# FLUIDIC_CTRL.net
KiCad netlist of a schematic drawn in Altium Designer
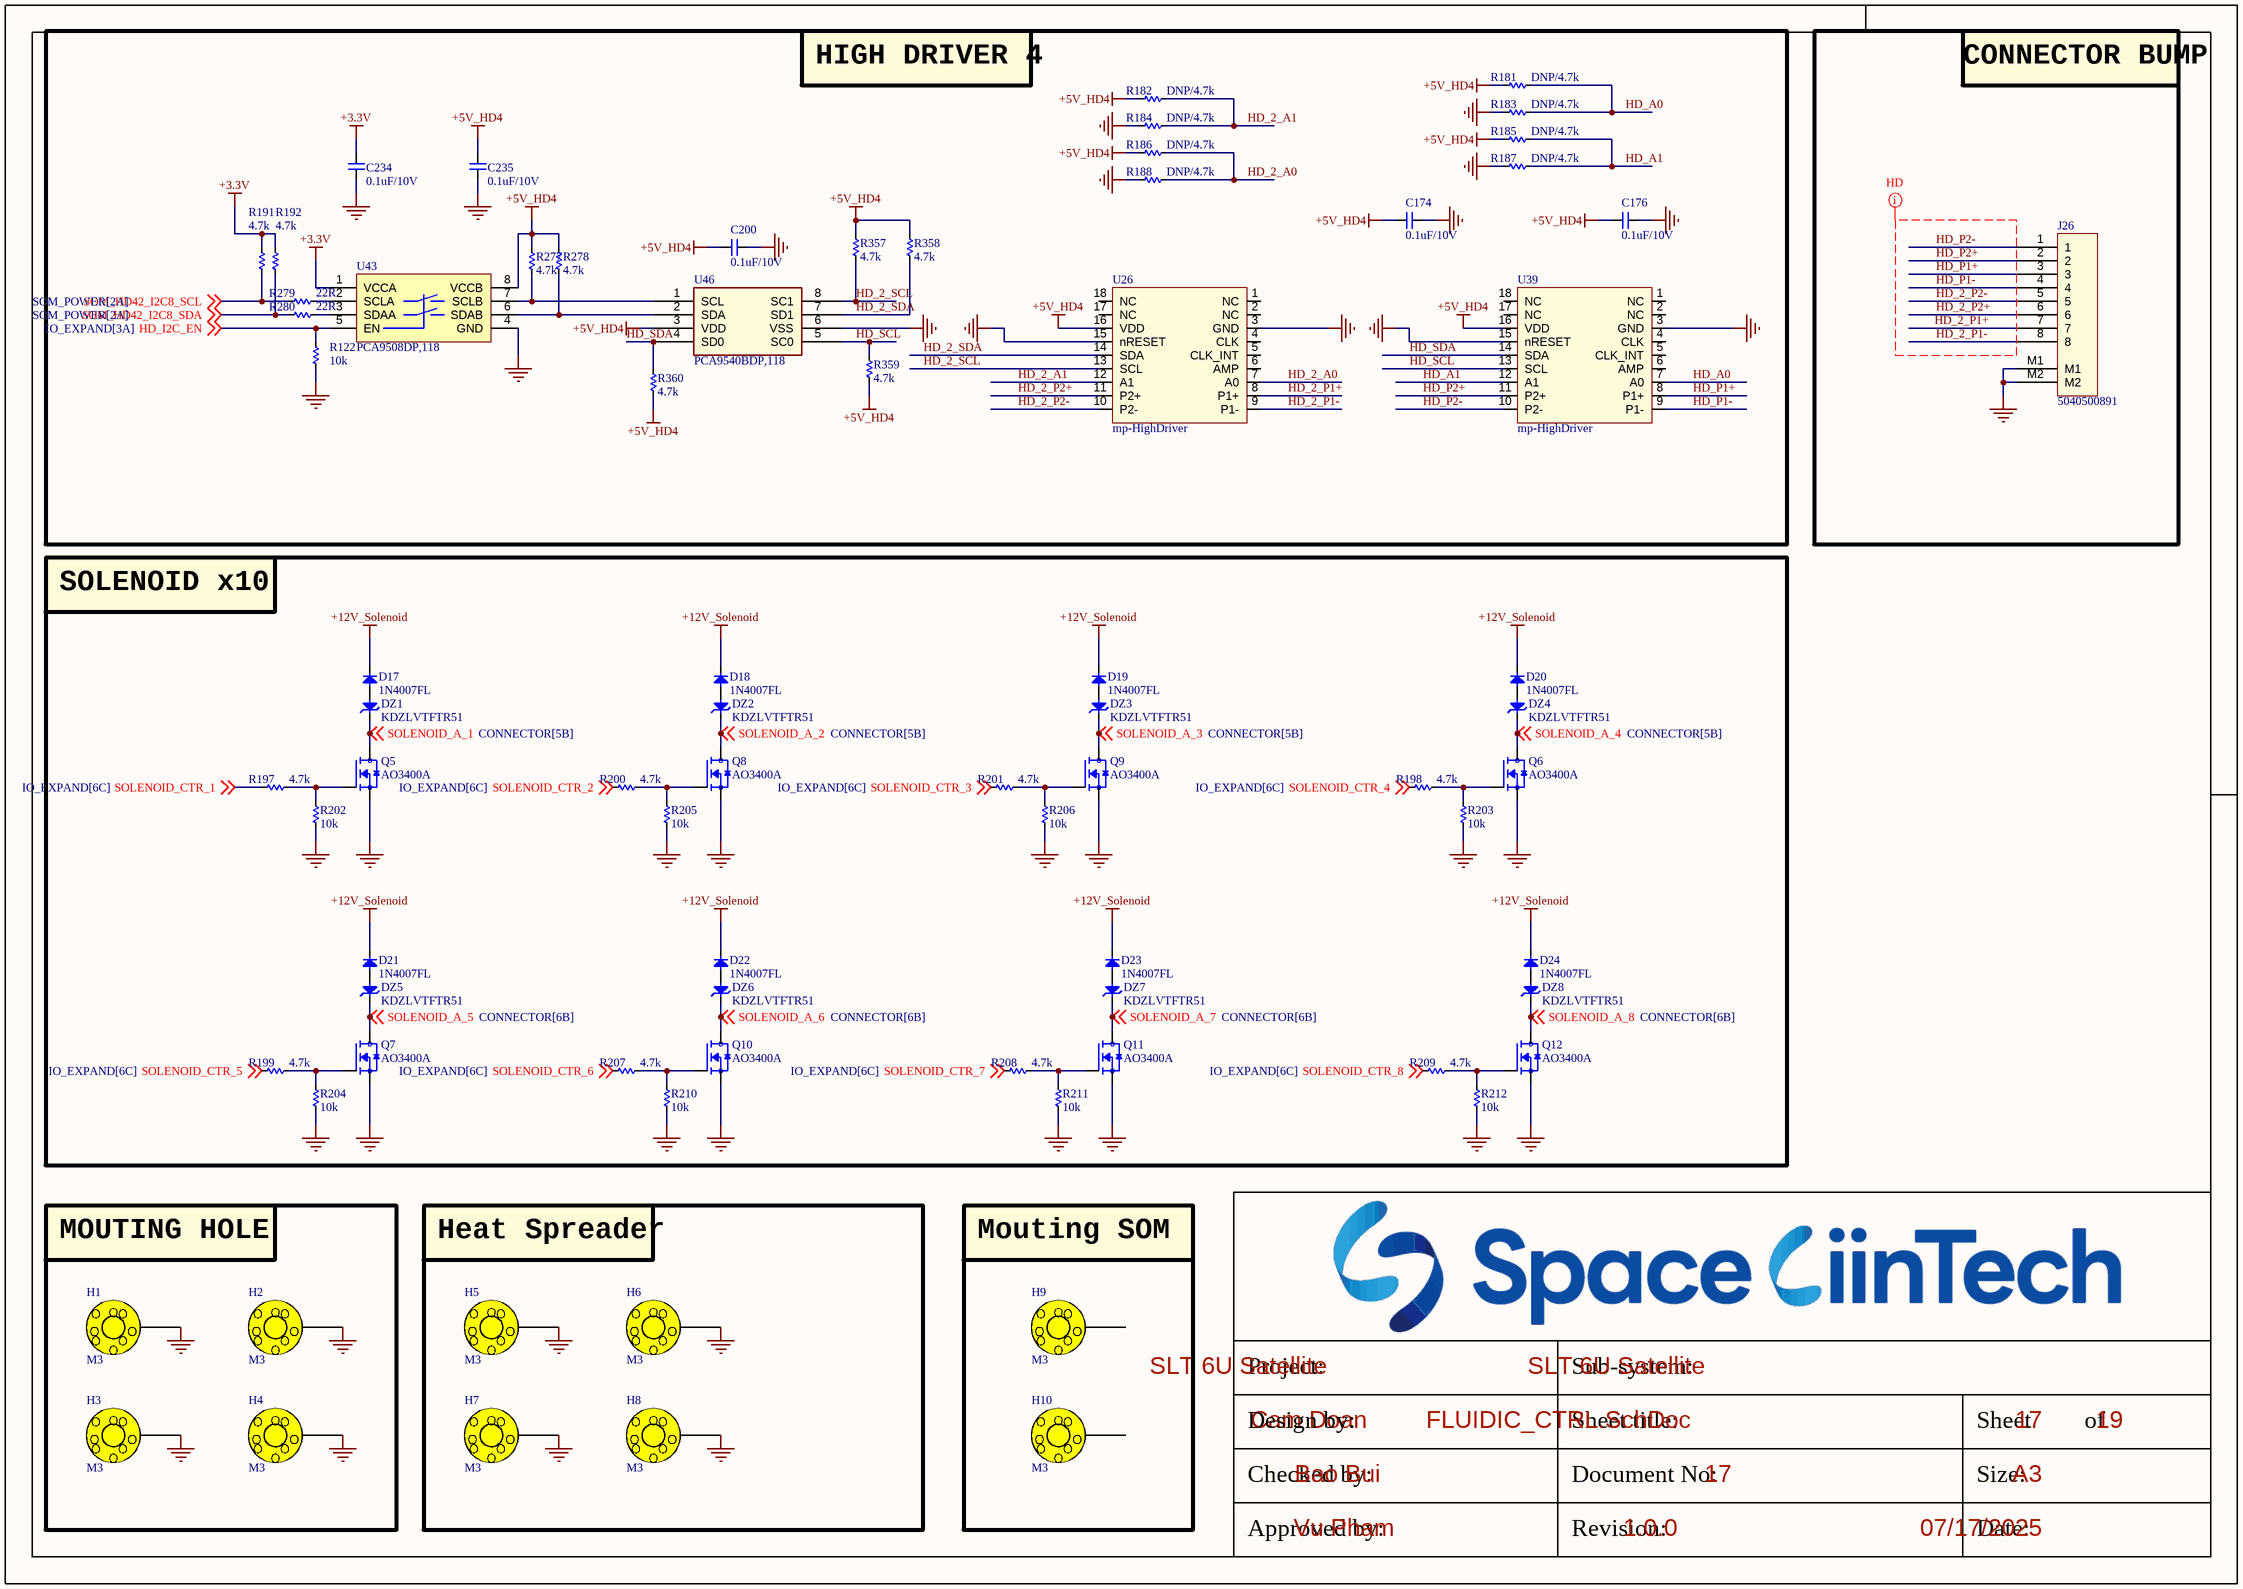
[diagram p0: FLUIDIC_CTRL.SchDoc]

(export (version "E")
  (design (tool "Eeschema 10.0.6"))
  (components
    (comp (ref "C174")
      (value "0.1uF/10V")
      (footprint "CAP_C_1005X60")
      (description "CAP CHIP")
      (libsource (lib "LABLIB") (part "_CAP_C_2"))
    )
    (comp (ref "C176")
      (value "0.1uF/10V")
      (footprint "CAP_C_1005X60")
      (description "CAP CHIP")
      (libsource (lib "LABLIB") (part "_CAP_C_2"))
    )
    (comp (ref "C200")
      (value "0.1uF/10V")
      (footprint "CAP_C_1005X60")
      (description "CAP CHIP")
      (libsource (lib "LABLIB") (part "_CAP_C_2"))
    )
    (comp (ref "C234")
      (value "0.1uF/10V")
      (footprint "CAP_C_1005X60")
      (description "CAP CHIP")
      (libsource (lib "LABLIB") (part "_CAP_C_2"))
    )
    (comp (ref "C235")
      (value "0.1uF/10V")
      (footprint "CAP_C_1005X60")
      (description "CAP CHIP")
      (libsource (lib "LABLIB") (part "_CAP_C_2"))
    )
    (comp (ref "D17")
      (value "1N4007FL")
      (footprint "DIO-SMD-106")
      (description "Default Diode")
      (fields (field (name "PUBLISHER") "Altium Limited"))
      (libsource (lib "LABLIB") (part "Diode SMD"))
    )
    (comp (ref "D18")
      (value "1N4007FL")
      (footprint "DIO-SMD-106")
      (description "Default Diode")
      (fields (field (name "PUBLISHER") "Altium Limited"))
      (libsource (lib "LABLIB") (part "Diode SMD"))
    )
    (comp (ref "D19")
      (value "1N4007FL")
      (footprint "DIO-SMD-106")
      (description "Default Diode")
      (fields (field (name "PUBLISHER") "Altium Limited"))
      (libsource (lib "LABLIB") (part "Diode SMD"))
    )
    (comp (ref "D20")
      (value "1N4007FL")
      (footprint "DIO-SMD-106")
      (description "Default Diode")
      (fields (field (name "PUBLISHER") "Altium Limited"))
      (libsource (lib "LABLIB") (part "Diode SMD"))
    )
    (comp (ref "D21")
      (value "1N4007FL")
      (footprint "DIO-SMD-106")
      (description "Default Diode")
      (fields (field (name "PUBLISHER") "Altium Limited"))
      (libsource (lib "LABLIB") (part "Diode SMD"))
    )
    (comp (ref "D22")
      (value "1N4007FL")
      (footprint "DIO-SMD-106")
      (description "Default Diode")
      (fields (field (name "PUBLISHER") "Altium Limited"))
      (libsource (lib "LABLIB") (part "Diode SMD"))
    )
    (comp (ref "D23")
      (value "1N4007FL")
      (footprint "DIO-SMD-106")
      (description "Default Diode")
      (fields (field (name "PUBLISHER") "Altium Limited"))
      (libsource (lib "LABLIB") (part "Diode SMD"))
    )
    (comp (ref "D24")
      (value "1N4007FL")
      (footprint "DIO-SMD-106")
      (description "Default Diode")
      (fields (field (name "PUBLISHER") "Altium Limited"))
      (libsource (lib "LABLIB") (part "Diode SMD"))
    )
    (comp (ref "DZ1")
      (value "KDZLVTFTR51")
      (footprint "DIO-0.5A-SMALL")
      (description "Zenner")
      (libsource (lib "LABLIB") (part "DIODE Zener"))
    )
    (comp (ref "DZ2")
      (value "KDZLVTFTR51")
      (footprint "DIO-0.5A-SMALL")
      (description "Zenner")
      (libsource (lib "LABLIB") (part "DIODE Zener"))
    )
    (comp (ref "DZ3")
      (value "KDZLVTFTR51")
      (footprint "DIO-0.5A-SMALL")
      (description "Zenner")
      (libsource (lib "LABLIB") (part "DIODE Zener"))
    )
    (comp (ref "DZ4")
      (value "KDZLVTFTR51")
      (footprint "DIO-0.5A-SMALL")
      (description "Zenner")
      (libsource (lib "LABLIB") (part "DIODE Zener"))
    )
    (comp (ref "DZ5")
      (value "KDZLVTFTR51")
      (footprint "DIO-0.5A-SMALL")
      (description "Zenner")
      (libsource (lib "LABLIB") (part "DIODE Zener"))
    )
    (comp (ref "DZ6")
      (value "KDZLVTFTR51")
      (footprint "DIO-0.5A-SMALL")
      (description "Zenner")
      (libsource (lib "LABLIB") (part "DIODE Zener"))
    )
    (comp (ref "DZ7")
      (value "KDZLVTFTR51")
      (footprint "DIO-0.5A-SMALL")
      (description "Zenner")
      (libsource (lib "LABLIB") (part "DIODE Zener"))
    )
    (comp (ref "DZ8")
      (value "KDZLVTFTR51")
      (footprint "DIO-0.5A-SMALL")
      (description "Zenner")
      (libsource (lib "LABLIB") (part "DIODE Zener"))
    )
    (comp (ref "H1") (value "M3") (footprint "HEX-M3") (libsource (lib "hex_M3") (part "HEX-M3")))
    (comp (ref "H2") (value "M3") (footprint "HEX-M3") (libsource (lib "hex_M3") (part "HEX-M3")))
    (comp (ref "H3") (value "M3") (footprint "HEX-M3") (libsource (lib "hex_M3") (part "HEX-M3")))
    (comp (ref "H4") (value "M3") (footprint "HEX-M3") (libsource (lib "hex_M3") (part "HEX-M3")))
    (comp (ref "H5") (value "M3") (footprint "HEX-M3") (libsource (lib "hex_M3") (part "HEX-M3")))
    (comp (ref "H6") (value "M3") (footprint "HEX-M3") (libsource (lib "hex_M3") (part "HEX-M3")))
    (comp (ref "H7") (value "M3") (footprint "HEX-M3") (libsource (lib "hex_M3") (part "HEX-M3")))
    (comp (ref "H8") (value "M3") (footprint "HEX-M3") (libsource (lib "hex_M3") (part "HEX-M3")))
    (comp (ref "H9")
      (value "M3")
      (footprint "Testpoint_TH_D400H200")
      (libsource (lib "hex_M3") (part "HEX-M3"))
    )
    (comp (ref "H10")
      (value "M3")
      (footprint "Testpoint_TH_D400H200")
      (libsource (lib "hex_M3") (part "HEX-M3"))
    )
    (comp (ref "J26")
      (value "5040500891")
      (footprint "MOLEX_5040500891")
      (libsource (lib "LABLIB") (part "Header 8x1_2M"))
    )
    (comp (ref "Q5")
      (value "AO3400A")
      (footprint "SOT95P240X120-3N")
      (description "N-Channel 30 V 5.7A (Ta) 1.4W (Ta) Surface Mount SOT-23-3")
      (fields (field (name "MF") "Alpha & Omega Semiconductor"))
      (libsource (lib "new_component") (part "MOSFET_N"))
    )
    (comp (ref "Q6")
      (value "AO3400A")
      (footprint "SOT95P240X120-3N")
      (description "N-Channel 30 V 5.7A (Ta) 1.4W (Ta) Surface Mount SOT-23-3")
      (fields (field (name "MF") "Alpha & Omega Semiconductor"))
      (libsource (lib "new_component") (part "MOSFET_N"))
    )
    (comp (ref "Q7")
      (value "AO3400A")
      (footprint "SOT95P240X120-3N")
      (description "N-Channel 30 V 5.7A (Ta) 1.4W (Ta) Surface Mount SOT-23-3")
      (fields (field (name "MF") "Alpha & Omega Semiconductor"))
      (libsource (lib "new_component") (part "MOSFET_N"))
    )
    (comp (ref "Q8")
      (value "AO3400A")
      (footprint "SOT95P240X120-3N")
      (description "N-Channel 30 V 5.7A (Ta) 1.4W (Ta) Surface Mount SOT-23-3")
      (fields (field (name "MF") "Alpha & Omega Semiconductor"))
      (libsource (lib "new_component") (part "MOSFET_N"))
    )
    (comp (ref "Q9")
      (value "AO3400A")
      (footprint "SOT95P240X120-3N")
      (description "N-Channel 30 V 5.7A (Ta) 1.4W (Ta) Surface Mount SOT-23-3")
      (fields (field (name "MF") "Alpha & Omega Semiconductor"))
      (libsource (lib "new_component") (part "MOSFET_N"))
    )
    (comp (ref "Q10")
      (value "AO3400A")
      (footprint "SOT95P240X120-3N")
      (description "N-Channel 30 V 5.7A (Ta) 1.4W (Ta) Surface Mount SOT-23-3")
      (fields (field (name "MF") "Alpha & Omega Semiconductor"))
      (libsource (lib "new_component") (part "MOSFET_N"))
    )
    (comp (ref "Q11")
      (value "AO3400A")
      (footprint "SOT95P240X120-3N")
      (description "N-Channel 30 V 5.7A (Ta) 1.4W (Ta) Surface Mount SOT-23-3")
      (fields (field (name "MF") "Alpha & Omega Semiconductor"))
      (libsource (lib "new_component") (part "MOSFET_N"))
    )
    (comp (ref "Q12")
      (value "AO3400A")
      (footprint "SOT95P240X120-3N")
      (description "N-Channel 30 V 5.7A (Ta) 1.4W (Ta) Surface Mount SOT-23-3")
      (fields (field (name "MF") "Alpha & Omega Semiconductor"))
      (libsource (lib "new_component") (part "MOSFET_N"))
    )
    (comp (ref "R122")
      (value "10k")
      (footprint "RES_C_1005X40")
      (description "RES")
      (libsource (lib "LABLIB") (part "_RES_B_2"))
    )
    (comp (ref "R181")
      (value "DNP/4.7k")
      (footprint "RES_C_1005X40")
      (description "RES")
      (libsource (lib "LABLIB") (part "_RES_B_2"))
    )
    (comp (ref "R182")
      (value "DNP/4.7k")
      (footprint "RES_C_1005X40")
      (description "RES")
      (libsource (lib "LABLIB") (part "_RES_B_2"))
    )
    (comp (ref "R183")
      (value "DNP/4.7k")
      (footprint "RES_C_1005X40")
      (description "RES")
      (libsource (lib "LABLIB") (part "_RES_B_2"))
    )
    (comp (ref "R184")
      (value "DNP/4.7k")
      (footprint "RES_C_1005X40")
      (description "RES")
      (libsource (lib "LABLIB") (part "_RES_B_2"))
    )
    (comp (ref "R185")
      (value "DNP/4.7k")
      (footprint "RES_C_1005X40")
      (description "RES")
      (libsource (lib "LABLIB") (part "_RES_B_2"))
    )
    (comp (ref "R186")
      (value "DNP/4.7k")
      (footprint "RES_C_1005X40")
      (description "RES")
      (libsource (lib "LABLIB") (part "_RES_B_2"))
    )
    (comp (ref "R187")
      (value "DNP/4.7k")
      (footprint "RES_C_1005X40")
      (description "RES")
      (libsource (lib "LABLIB") (part "_RES_B_2"))
    )
    (comp (ref "R188")
      (value "DNP/4.7k")
      (footprint "RES_C_1005X40")
      (description "RES")
      (libsource (lib "LABLIB") (part "_RES_B_2"))
    )
    (comp (ref "R191")
      (value "4.7k")
      (footprint "RES_C_1005X40")
      (description "RES")
      (libsource (lib "LABLIB") (part "_RES_B_2"))
    )
    (comp (ref "R192")
      (value "4.7k")
      (footprint "RES_C_1005X40")
      (description "RES")
      (libsource (lib "LABLIB") (part "_RES_B_2"))
    )
    (comp (ref "R197")
      (value "4.7k")
      (footprint "RES_C_1005X40")
      (description "RES")
      (libsource (lib "LABLIB") (part "_RES_B_2"))
    )
    (comp (ref "R198")
      (value "4.7k")
      (footprint "RES_C_1005X40")
      (description "RES")
      (libsource (lib "LABLIB") (part "_RES_B_2"))
    )
    (comp (ref "R199")
      (value "4.7k")
      (footprint "RES_C_1005X40")
      (description "RES")
      (libsource (lib "LABLIB") (part "_RES_B_2"))
    )
    (comp (ref "R200")
      (value "4.7k")
      (footprint "RES_C_1005X40")
      (description "RES")
      (libsource (lib "LABLIB") (part "_RES_B_2"))
    )
    (comp (ref "R201")
      (value "4.7k")
      (footprint "RES_C_1005X40")
      (description "RES")
      (libsource (lib "LABLIB") (part "_RES_B_2"))
    )
    (comp (ref "R202")
      (value "10k")
      (footprint "RES_C_1005X40")
      (description "RES")
      (libsource (lib "LABLIB") (part "_RES_B_2"))
    )
    (comp (ref "R203")
      (value "10k")
      (footprint "RES_C_1005X40")
      (description "RES")
      (libsource (lib "LABLIB") (part "_RES_B_2"))
    )
    (comp (ref "R204")
      (value "10k")
      (footprint "RES_C_1005X40")
      (description "RES")
      (libsource (lib "LABLIB") (part "_RES_B_2"))
    )
    (comp (ref "R205")
      (value "10k")
      (footprint "RES_C_1005X40")
      (description "RES")
      (libsource (lib "LABLIB") (part "_RES_B_2"))
    )
    (comp (ref "R206")
      (value "10k")
      (footprint "RES_C_1005X40")
      (description "RES")
      (libsource (lib "LABLIB") (part "_RES_B_2"))
    )
    (comp (ref "R207")
      (value "4.7k")
      (footprint "RES_C_1005X40")
      (description "RES")
      (libsource (lib "LABLIB") (part "_RES_B_2"))
    )
    (comp (ref "R208")
      (value "4.7k")
      (footprint "RES_C_1005X40")
      (description "RES")
      (libsource (lib "LABLIB") (part "_RES_B_2"))
    )
    (comp (ref "R209")
      (value "4.7k")
      (footprint "RES_C_1005X40")
      (description "RES")
      (libsource (lib "LABLIB") (part "_RES_B_2"))
    )
    (comp (ref "R210")
      (value "10k")
      (footprint "RES_C_1005X40")
      (description "RES")
      (libsource (lib "LABLIB") (part "_RES_B_2"))
    )
    (comp (ref "R211")
      (value "10k")
      (footprint "RES_C_1005X40")
      (description "RES")
      (libsource (lib "LABLIB") (part "_RES_B_2"))
    )
    (comp (ref "R212")
      (value "10k")
      (footprint "RES_C_1005X40")
      (description "RES")
      (libsource (lib "LABLIB") (part "_RES_B_2"))
    )
    (comp (ref "R277")
      (value "4.7k")
      (footprint "RES_C_1005X40")
      (description "RES")
      (libsource (lib "LABLIB") (part "_RES_B_2"))
    )
    (comp (ref "R278")
      (value "4.7k")
      (footprint "RES_C_1005X40")
      (description "RES")
      (libsource (lib "LABLIB") (part "_RES_B_2"))
    )
    (comp (ref "R279")
      (value "22R")
      (footprint "RES_C_1005X40")
      (description "RES")
      (libsource (lib "LABLIB") (part "_RES_B_2"))
    )
    (comp (ref "R280")
      (value "22R")
      (footprint "RES_C_1005X40")
      (description "RES")
      (libsource (lib "LABLIB") (part "_RES_B_2"))
    )
    (comp (ref "R357")
      (value "4.7k")
      (footprint "RES_C_1005X40")
      (description "RES")
      (libsource (lib "LABLIB") (part "_RES_B_2"))
    )
    (comp (ref "R358")
      (value "4.7k")
      (footprint "RES_C_1005X40")
      (description "RES")
      (libsource (lib "LABLIB") (part "_RES_B_2"))
    )
    (comp (ref "R359")
      (value "4.7k")
      (footprint "RES_C_1005X40")
      (description "RES")
      (libsource (lib "LABLIB") (part "_RES_B_2"))
    )
    (comp (ref "R360")
      (value "4.7k")
      (footprint "RES_C_1005X40")
      (description "RES")
      (libsource (lib "LABLIB") (part "_RES_B_2"))
    )
    (comp (ref "U26")
      (value "mp-HighDriver")
      (footprint "MP_HIGHDRIVER")
      (libsource (lib "new_component") (part "mp-HighDriver"))
    )
    (comp (ref "U39")
      (value "mp-HighDriver")
      (footprint "MP_HIGHDRIVER")
      (libsource (lib "new_component") (part "mp-HighDriver"))
    )
    (comp (ref "U43")
      (value "PCA9508DP,118")
      (footprint "TSOP8")
      (libsource (lib "EXP_HW_V3") (part "PCA9508DP,118"))
    )
    (comp (ref "U46")
      (value "PCA9540BDP,118")
      (footprint "SOP65P510X110X300W-8")
      (description "IC INTERFACE SPECIALIZED")
      (libsource (lib "LABLIB") (part "IC_I2C_Mux_PCA9540BDP,118"))
    )
  )
  (nets
    (net (code "1") (name "+3.3V") (class "Default")
      (node (ref "C234") (pin "2") (pinfunction "2_2") (pintype "passive"))
      (node (ref "R191") (pin "1") (pinfunction "1_1") (pintype "passive"))
      (node (ref "R192") (pin "1") (pinfunction "1_1") (pintype "passive"))
      (node (ref "U43") (pin "1") (pinfunction "VCCA_1") (pintype "passive"))
    )
    (net (code "2") (name "+5V_HD4") (class "Default")
      (node (ref "C174") (pin "2") (pinfunction "2_2") (pintype "passive"))
      (node (ref "C176") (pin "2") (pinfunction "2_2") (pintype "passive"))
      (node (ref "C200") (pin "2") (pinfunction "2_2") (pintype "passive"))
      (node (ref "C235") (pin "2") (pinfunction "2_2") (pintype "passive"))
      (node (ref "R181") (pin "1") (pinfunction "1_1") (pintype "passive"))
      (node (ref "R182") (pin "1") (pinfunction "1_1") (pintype "passive"))
      (node (ref "R185") (pin "1") (pinfunction "1_1") (pintype "passive"))
      (node (ref "R186") (pin "1") (pinfunction "1_1") (pintype "passive"))
      (node (ref "R277") (pin "1") (pinfunction "1_1") (pintype "passive"))
      (node (ref "R278") (pin "1") (pinfunction "1_1") (pintype "passive"))
      (node (ref "R357") (pin "1") (pinfunction "1_1") (pintype "passive"))
      (node (ref "R358") (pin "1") (pinfunction "1_1") (pintype "passive"))
      (node (ref "R359") (pin "1") (pinfunction "1_1") (pintype "passive"))
      (node (ref "R360") (pin "1") (pinfunction "1_1") (pintype "passive"))
      (node (ref "U26") (pin "16") (pinfunction "VDD_16") (pintype "power_in"))
      (node (ref "U39") (pin "16") (pinfunction "VDD_16") (pintype "power_in"))
      (node (ref "U43") (pin "8") (pinfunction "VCCB_8") (pintype "passive"))
      (node (ref "U46") (pin "3") (pinfunction "VDD_3") (pintype "passive"))
    )
    (net (code "3") (name "+12V_Solenoid") (class "Default")
      (node (ref "D17") (pin "1") (pinfunction "K_1") (pintype "passive"))
      (node (ref "D18") (pin "1") (pinfunction "K_1") (pintype "passive"))
      (node (ref "D19") (pin "1") (pinfunction "K_1") (pintype "passive"))
      (node (ref "D20") (pin "1") (pinfunction "K_1") (pintype "passive"))
      (node (ref "D21") (pin "1") (pinfunction "K_1") (pintype "passive"))
      (node (ref "D22") (pin "1") (pinfunction "K_1") (pintype "passive"))
      (node (ref "D23") (pin "1") (pinfunction "K_1") (pintype "passive"))
      (node (ref "D24") (pin "1") (pinfunction "K_1") (pintype "passive"))
    )
    (net (code "4") (name "/HD_2_A0") (class "Default")
      (node (ref "R186") (pin "2") (pinfunction "2_2") (pintype "passive"))
      (node (ref "R188") (pin "2") (pinfunction "2_2") (pintype "passive"))
      (node (ref "U26") (pin "7") (pinfunction "A0_7") (pintype "passive"))
    )
    (net (code "5") (name "/HD_2_A1") (class "Default")
      (node (ref "R182") (pin "2") (pinfunction "2_2") (pintype "passive"))
      (node (ref "R184") (pin "2") (pinfunction "2_2") (pintype "passive"))
      (node (ref "U26") (pin "12") (pinfunction "A1_12") (pintype "passive"))
    )
    (net (code "6") (name "/HD_2_P1+") (class "Default")
      (node (ref "J26") (pin "7") (pinfunction "7_7") (pintype "passive"))
      (node (ref "U26") (pin "8") (pinfunction "P1+_8") (pintype "passive"))
    )
    (net (code "7") (name "/HD_2_P1-") (class "Default")
      (node (ref "J26") (pin "8") (pinfunction "8_8") (pintype "passive"))
      (node (ref "U26") (pin "9") (pinfunction "P1-_9") (pintype "passive"))
    )
    (net (code "8") (name "/HD_2_P2+") (class "Default")
      (node (ref "J26") (pin "6") (pinfunction "6_6") (pintype "passive"))
      (node (ref "U26") (pin "11") (pinfunction "P2+_11") (pintype "passive"))
    )
    (net (code "9") (name "/HD_2_P2-") (class "Default")
      (node (ref "J26") (pin "5") (pinfunction "5_5") (pintype "passive"))
      (node (ref "U26") (pin "10") (pinfunction "P2-_10") (pintype "passive"))
    )
    (net (code "10") (name "/HD_2_SCL") (class "Default")
      (node (ref "R357") (pin "2") (pinfunction "2_2") (pintype "passive"))
      (node (ref "U26") (pin "13") (pinfunction "SCL_13") (pintype "passive"))
      (node (ref "U46") (pin "8") (pinfunction "SC1_8") (pintype "passive"))
    )
    (net (code "11") (name "/HD_2_SDA") (class "Default")
      (node (ref "R358") (pin "2") (pinfunction "2_2") (pintype "passive"))
      (node (ref "U26") (pin "14") (pinfunction "SDA_14") (pintype "passive"))
      (node (ref "U46") (pin "7") (pinfunction "SD1_7") (pintype "passive"))
    )
    (net (code "12") (name "/HD_A0") (class "Default")
      (node (ref "R181") (pin "2") (pinfunction "2_2") (pintype "passive"))
      (node (ref "R183") (pin "2") (pinfunction "2_2") (pintype "passive"))
      (node (ref "U39") (pin "7") (pinfunction "A0_7") (pintype "passive"))
    )
    (net (code "13") (name "/HD_A1") (class "Default")
      (node (ref "R185") (pin "2") (pinfunction "2_2") (pintype "passive"))
      (node (ref "R187") (pin "2") (pinfunction "2_2") (pintype "passive"))
      (node (ref "U39") (pin "12") (pinfunction "A1_12") (pintype "passive"))
    )
    (net (code "14") (name "/HD_P1+") (class "Default")
      (node (ref "J26") (pin "3") (pinfunction "3_3") (pintype "passive"))
      (node (ref "U39") (pin "8") (pinfunction "P1+_8") (pintype "passive"))
    )
    (net (code "15") (name "/HD_P1-") (class "Default")
      (node (ref "J26") (pin "4") (pinfunction "4_4") (pintype "passive"))
      (node (ref "U39") (pin "9") (pinfunction "P1-_9") (pintype "passive"))
    )
    (net (code "16") (name "/HD_P2+") (class "Default")
      (node (ref "J26") (pin "2") (pinfunction "2_2") (pintype "passive"))
      (node (ref "U39") (pin "11") (pinfunction "P2+_11") (pintype "passive"))
    )
    (net (code "17") (name "/HD_P2-") (class "Default")
      (node (ref "J26") (pin "1") (pinfunction "1_1") (pintype "passive"))
      (node (ref "U39") (pin "10") (pinfunction "P2-_10") (pintype "passive"))
    )
    (net (code "18") (name "/HD_SCL") (class "Default")
      (node (ref "R359") (pin "2") (pinfunction "2_2") (pintype "passive"))
      (node (ref "U39") (pin "13") (pinfunction "SCL_13") (pintype "passive"))
      (node (ref "U46") (pin "5") (pinfunction "SC0_5") (pintype "passive"))
    )
    (net (code "19") (name "/HD_SDA") (class "Default")
      (node (ref "R360") (pin "2") (pinfunction "2_2") (pintype "passive"))
      (node (ref "U39") (pin "14") (pinfunction "SDA_14") (pintype "passive"))
      (node (ref "U46") (pin "4") (pinfunction "SD0_4") (pintype "passive"))
    )
    (net (code "20") (name "GND") (class "Default")
      (node (ref "C174") (pin "1") (pinfunction "1_1") (pintype "passive"))
      (node (ref "C176") (pin "1") (pinfunction "1_1") (pintype "passive"))
      (node (ref "C200") (pin "1") (pinfunction "1_1") (pintype "passive"))
      (node (ref "C234") (pin "1") (pinfunction "1_1") (pintype "passive"))
      (node (ref "C235") (pin "1") (pinfunction "1_1") (pintype "passive"))
      (node (ref "H1") (pin "1") (pinfunction "1_1") (pintype "power_in"))
      (node (ref "H2") (pin "1") (pinfunction "1_1") (pintype "power_in"))
      (node (ref "H3") (pin "1") (pinfunction "1_1") (pintype "power_in"))
      (node (ref "H4") (pin "1") (pinfunction "1_1") (pintype "power_in"))
      (node (ref "H5") (pin "1") (pinfunction "1_1") (pintype "power_in"))
      (node (ref "H6") (pin "1") (pinfunction "1_1") (pintype "power_in"))
      (node (ref "H7") (pin "1") (pinfunction "1_1") (pintype "power_in"))
      (node (ref "H8") (pin "1") (pinfunction "1_1") (pintype "power_in"))
      (node (ref "J26") (pin "M1") (pinfunction "M1_M1") (pintype "passive"))
      (node (ref "J26") (pin "M2") (pinfunction "M2_M2") (pintype "passive"))
      (node (ref "Q10") (pin "2") (pinfunction "S_2") (pintype "passive"))
      (node (ref "Q11") (pin "2") (pinfunction "S_2") (pintype "passive"))
      (node (ref "Q12") (pin "2") (pinfunction "S_2") (pintype "passive"))
      (node (ref "Q5") (pin "2") (pinfunction "S_2") (pintype "passive"))
      (node (ref "Q6") (pin "2") (pinfunction "S_2") (pintype "passive"))
      (node (ref "Q7") (pin "2") (pinfunction "S_2") (pintype "passive"))
      (node (ref "Q8") (pin "2") (pinfunction "S_2") (pintype "passive"))
      (node (ref "Q9") (pin "2") (pinfunction "S_2") (pintype "passive"))
      (node (ref "R122") (pin "2") (pinfunction "2_2") (pintype "passive"))
      (node (ref "R183") (pin "1") (pinfunction "1_1") (pintype "passive"))
      (node (ref "R184") (pin "1") (pinfunction "1_1") (pintype "passive"))
      (node (ref "R187") (pin "1") (pinfunction "1_1") (pintype "passive"))
      (node (ref "R188") (pin "1") (pinfunction "1_1") (pintype "passive"))
      (node (ref "R202") (pin "1") (pinfunction "1_1") (pintype "passive"))
      (node (ref "R203") (pin "1") (pinfunction "1_1") (pintype "passive"))
      (node (ref "R204") (pin "1") (pinfunction "1_1") (pintype "passive"))
      (node (ref "R205") (pin "1") (pinfunction "1_1") (pintype "passive"))
      (node (ref "R206") (pin "1") (pinfunction "1_1") (pintype "passive"))
      (node (ref "R210") (pin "1") (pinfunction "1_1") (pintype "passive"))
      (node (ref "R211") (pin "1") (pinfunction "1_1") (pintype "passive"))
      (node (ref "R212") (pin "1") (pinfunction "1_1") (pintype "passive"))
      (node (ref "U26") (pin "15") (pinfunction "nRESET_15") (pintype "passive"))
      (node (ref "U26") (pin "3") (pinfunction "GND_3") (pintype "power_in"))
      (node (ref "U39") (pin "15") (pinfunction "nRESET_15") (pintype "passive"))
      (node (ref "U39") (pin "3") (pinfunction "GND_3") (pintype "power_in"))
      (node (ref "U43") (pin "4") (pinfunction "GND_4") (pintype "passive"))
      (node (ref "U46") (pin "6") (pinfunction "VSS_6") (pintype "passive"))
    )
    (net (code "21") (name "HD_I2C_EN") (class "Default")
      (node (ref "R122") (pin "1") (pinfunction "1_1") (pintype "passive"))
      (node (ref "U43") (pin "5") (pinfunction "EN_5") (pintype "passive"))
    )
    (net (code "22") (name "Net-(D17-A)") (class "Default")
      (node (ref "D17") (pin "2") (pinfunction "A_2") (pintype "passive"))
      (node (ref "DZ1") (pin "2") (pinfunction "A_2") (pintype "passive"))
    )
    (net (code "23") (name "Net-(D18-A)") (class "Default")
      (node (ref "D18") (pin "2") (pinfunction "A_2") (pintype "passive"))
      (node (ref "DZ2") (pin "2") (pinfunction "A_2") (pintype "passive"))
    )
    (net (code "24") (name "Net-(D19-A)") (class "Default")
      (node (ref "D19") (pin "2") (pinfunction "A_2") (pintype "passive"))
      (node (ref "DZ3") (pin "2") (pinfunction "A_2") (pintype "passive"))
    )
    (net (code "25") (name "Net-(D20-A)") (class "Default")
      (node (ref "D20") (pin "2") (pinfunction "A_2") (pintype "passive"))
      (node (ref "DZ4") (pin "2") (pinfunction "A_2") (pintype "passive"))
    )
    (net (code "26") (name "Net-(D21-A)") (class "Default")
      (node (ref "D21") (pin "2") (pinfunction "A_2") (pintype "passive"))
      (node (ref "DZ5") (pin "2") (pinfunction "A_2") (pintype "passive"))
    )
    (net (code "27") (name "Net-(D22-A)") (class "Default")
      (node (ref "D22") (pin "2") (pinfunction "A_2") (pintype "passive"))
      (node (ref "DZ6") (pin "2") (pinfunction "A_2") (pintype "passive"))
    )
    (net (code "28") (name "Net-(D23-A)") (class "Default")
      (node (ref "D23") (pin "2") (pinfunction "A_2") (pintype "passive"))
      (node (ref "DZ7") (pin "2") (pinfunction "A_2") (pintype "passive"))
    )
    (net (code "29") (name "Net-(D24-A)") (class "Default")
      (node (ref "D24") (pin "2") (pinfunction "A_2") (pintype "passive"))
      (node (ref "DZ8") (pin "2") (pinfunction "A_2") (pintype "passive"))
    )
    (net (code "30") (name "Net-(Q5-G)") (class "Default")
      (node (ref "Q5") (pin "1") (pinfunction "G_1") (pintype "passive"))
      (node (ref "R197") (pin "1") (pinfunction "1_1") (pintype "passive"))
      (node (ref "R202") (pin "2") (pinfunction "2_2") (pintype "passive"))
    )
    (net (code "31") (name "Net-(Q6-G)") (class "Default")
      (node (ref "Q6") (pin "1") (pinfunction "G_1") (pintype "passive"))
      (node (ref "R198") (pin "1") (pinfunction "1_1") (pintype "passive"))
      (node (ref "R203") (pin "2") (pinfunction "2_2") (pintype "passive"))
    )
    (net (code "32") (name "Net-(Q7-G)") (class "Default")
      (node (ref "Q7") (pin "1") (pinfunction "G_1") (pintype "passive"))
      (node (ref "R199") (pin "1") (pinfunction "1_1") (pintype "passive"))
      (node (ref "R204") (pin "2") (pinfunction "2_2") (pintype "passive"))
    )
    (net (code "33") (name "Net-(Q8-G)") (class "Default")
      (node (ref "Q8") (pin "1") (pinfunction "G_1") (pintype "passive"))
      (node (ref "R200") (pin "1") (pinfunction "1_1") (pintype "passive"))
      (node (ref "R205") (pin "2") (pinfunction "2_2") (pintype "passive"))
    )
    (net (code "34") (name "Net-(Q9-G)") (class "Default")
      (node (ref "Q9") (pin "1") (pinfunction "G_1") (pintype "passive"))
      (node (ref "R201") (pin "1") (pinfunction "1_1") (pintype "passive"))
      (node (ref "R206") (pin "2") (pinfunction "2_2") (pintype "passive"))
    )
    (net (code "35") (name "Net-(Q10-G)") (class "Default")
      (node (ref "Q10") (pin "1") (pinfunction "G_1") (pintype "passive"))
      (node (ref "R207") (pin "1") (pinfunction "1_1") (pintype "passive"))
      (node (ref "R210") (pin "2") (pinfunction "2_2") (pintype "passive"))
    )
    (net (code "36") (name "Net-(Q11-G)") (class "Default")
      (node (ref "Q11") (pin "1") (pinfunction "G_1") (pintype "passive"))
      (node (ref "R208") (pin "1") (pinfunction "1_1") (pintype "passive"))
      (node (ref "R211") (pin "2") (pinfunction "2_2") (pintype "passive"))
    )
    (net (code "37") (name "Net-(Q12-G)") (class "Default")
      (node (ref "Q12") (pin "1") (pinfunction "G_1") (pintype "passive"))
      (node (ref "R209") (pin "1") (pinfunction "1_1") (pintype "passive"))
      (node (ref "R212") (pin "2") (pinfunction "2_2") (pintype "passive"))
    )
    (net (code "38") (name "Net-(U43-SCLA)") (class "Default")
      (node (ref "R279") (pin "1") (pinfunction "1_1") (pintype "passive"))
      (node (ref "U43") (pin "2") (pinfunction "SCLA_2") (pintype "passive"))
    )
    (net (code "39") (name "Net-(U43-SCLB)") (class "Default")
      (node (ref "R277") (pin "2") (pinfunction "2_2") (pintype "passive"))
      (node (ref "U43") (pin "7") (pinfunction "SCLB_7") (pintype "passive"))
      (node (ref "U46") (pin "1") (pinfunction "SCL_1") (pintype "passive"))
    )
    (net (code "40") (name "Net-(U43-SDAA)") (class "Default")
      (node (ref "R280") (pin "1") (pinfunction "1_1") (pintype "passive"))
      (node (ref "U43") (pin "3") (pinfunction "SDAA_3") (pintype "passive"))
    )
    (net (code "41") (name "Net-(U43-SDAB)") (class "Default")
      (node (ref "R278") (pin "2") (pinfunction "2_2") (pintype "passive"))
      (node (ref "U43") (pin "6") (pinfunction "SDAB_6") (pintype "passive"))
      (node (ref "U46") (pin "2") (pinfunction "SDA_2") (pintype "passive"))
    )
    (net (code "42") (name "SOLENOID_A_1") (class "Default")
      (node (ref "DZ1") (pin "1") (pinfunction "K_1") (pintype "passive"))
      (node (ref "Q5") (pin "3") (pinfunction "D_3") (pintype "passive"))
    )
    (net (code "43") (name "SOLENOID_A_2") (class "Default")
      (node (ref "DZ2") (pin "1") (pinfunction "K_1") (pintype "passive"))
      (node (ref "Q8") (pin "3") (pinfunction "D_3") (pintype "passive"))
    )
    (net (code "44") (name "SOLENOID_A_3") (class "Default")
      (node (ref "DZ3") (pin "1") (pinfunction "K_1") (pintype "passive"))
      (node (ref "Q9") (pin "3") (pinfunction "D_3") (pintype "passive"))
    )
    (net (code "45") (name "SOLENOID_A_4") (class "Default")
      (node (ref "DZ4") (pin "1") (pinfunction "K_1") (pintype "passive"))
      (node (ref "Q6") (pin "3") (pinfunction "D_3") (pintype "passive"))
    )
    (net (code "46") (name "SOLENOID_A_5") (class "Default")
      (node (ref "DZ5") (pin "1") (pinfunction "K_1") (pintype "passive"))
      (node (ref "Q7") (pin "3") (pinfunction "D_3") (pintype "passive"))
    )
    (net (code "47") (name "SOLENOID_A_6") (class "Default")
      (node (ref "DZ6") (pin "1") (pinfunction "K_1") (pintype "passive"))
      (node (ref "Q10") (pin "3") (pinfunction "D_3") (pintype "passive"))
    )
    (net (code "48") (name "SOLENOID_A_7") (class "Default")
      (node (ref "DZ7") (pin "1") (pinfunction "K_1") (pintype "passive"))
      (node (ref "Q11") (pin "3") (pinfunction "D_3") (pintype "passive"))
    )
    (net (code "49") (name "SOLENOID_A_8") (class "Default")
      (node (ref "DZ8") (pin "1") (pinfunction "K_1") (pintype "passive"))
      (node (ref "Q12") (pin "3") (pinfunction "D_3") (pintype "passive"))
    )
    (net (code "50") (name "SOLENOID_CTR_1") (class "Default")
      (node (ref "R197") (pin "2") (pinfunction "2_2") (pintype "passive"))
    )
    (net (code "51") (name "SOLENOID_CTR_2") (class "Default")
      (node (ref "R200") (pin "2") (pinfunction "2_2") (pintype "passive"))
    )
    (net (code "52") (name "SOLENOID_CTR_3") (class "Default")
      (node (ref "R201") (pin "2") (pinfunction "2_2") (pintype "passive"))
    )
    (net (code "53") (name "SOLENOID_CTR_4") (class "Default")
      (node (ref "R198") (pin "2") (pinfunction "2_2") (pintype "passive"))
    )
    (net (code "54") (name "SOLENOID_CTR_5") (class "Default")
      (node (ref "R199") (pin "2") (pinfunction "2_2") (pintype "passive"))
    )
    (net (code "55") (name "SOLENOID_CTR_6") (class "Default")
      (node (ref "R207") (pin "2") (pinfunction "2_2") (pintype "passive"))
    )
    (net (code "56") (name "SOLENOID_CTR_7") (class "Default")
      (node (ref "R208") (pin "2") (pinfunction "2_2") (pintype "passive"))
    )
    (net (code "57") (name "SOLENOID_CTR_8") (class "Default")
      (node (ref "R209") (pin "2") (pinfunction "2_2") (pintype "passive"))
    )
    (net (code "58") (name "SOM_HD42_I2C8_SCL") (class "Default")
      (node (ref "R191") (pin "2") (pinfunction "2_2") (pintype "passive"))
      (node (ref "R279") (pin "2") (pinfunction "2_2") (pintype "passive"))
    )
    (net (code "59") (name "SOM_HD42_I2C8_SDA") (class "Default")
      (node (ref "R192") (pin "2") (pinfunction "2_2") (pintype "passive"))
      (node (ref "R280") (pin "2") (pinfunction "2_2") (pintype "passive"))
    )
    (net (code "60") (name "unconnected-(H9-Pad1)") (class "Default")
      (node (ref "H9") (pin "1") (pinfunction "1_1") (pintype "power_in"))
    )
    (net (code "61") (name "unconnected-(H10-Pad1)") (class "Default")
      (node (ref "H10") (pin "1") (pinfunction "1_1") (pintype "power_in"))
    )
    (net (code "62") (name "unconnected-(U26-AMP-Pad6)") (class "Default")
      (node (ref "U26") (pin "6") (pinfunction "AMP_6") (pintype "passive"))
    )
    (net (code "63") (name "unconnected-(U26-CLK-Pad4)") (class "Default")
      (node (ref "U26") (pin "4") (pinfunction "CLK_4") (pintype "passive"))
    )
    (net (code "64") (name "unconnected-(U26-CLK_INT-Pad5)") (class "Default")
      (node (ref "U26") (pin "5") (pinfunction "CLK_INT_5") (pintype "passive"))
    )
    (net (code "65") (name "unconnected-(U26-NC-Pad1)") (class "Default")
      (node (ref "U26") (pin "1") (pinfunction "NC_1") (pintype "passive"))
    )
    (net (code "66") (name "unconnected-(U26-NC-Pad2)") (class "Default")
      (node (ref "U26") (pin "2") (pinfunction "NC_2") (pintype "passive"))
    )
    (net (code "67") (name "unconnected-(U26-NC-Pad17)") (class "Default")
      (node (ref "U26") (pin "17") (pinfunction "NC_17") (pintype "passive"))
    )
    (net (code "68") (name "unconnected-(U26-NC-Pad18)") (class "Default")
      (node (ref "U26") (pin "18") (pinfunction "NC_18") (pintype "passive"))
    )
    (net (code "69") (name "unconnected-(U39-AMP-Pad6)") (class "Default")
      (node (ref "U39") (pin "6") (pinfunction "AMP_6") (pintype "passive"))
    )
    (net (code "70") (name "unconnected-(U39-CLK-Pad4)") (class "Default")
      (node (ref "U39") (pin "4") (pinfunction "CLK_4") (pintype "passive"))
    )
    (net (code "71") (name "unconnected-(U39-CLK_INT-Pad5)") (class "Default")
      (node (ref "U39") (pin "5") (pinfunction "CLK_INT_5") (pintype "passive"))
    )
    (net (code "72") (name "unconnected-(U39-NC-Pad1)") (class "Default")
      (node (ref "U39") (pin "1") (pinfunction "NC_1") (pintype "passive"))
    )
    (net (code "73") (name "unconnected-(U39-NC-Pad2)") (class "Default")
      (node (ref "U39") (pin "2") (pinfunction "NC_2") (pintype "passive"))
    )
    (net (code "74") (name "unconnected-(U39-NC-Pad17)") (class "Default")
      (node (ref "U39") (pin "17") (pinfunction "NC_17") (pintype "passive"))
    )
    (net (code "75") (name "unconnected-(U39-NC-Pad18)") (class "Default")
      (node (ref "U39") (pin "18") (pinfunction "NC_18") (pintype "passive"))
    )
  )
)
